# sender_einfach_12v.net
KiCad netlist of a schematic drawn in EAGLE
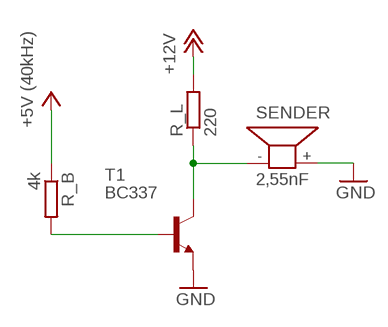
[diagram p0: schematic, sheet 1]

(export (version "E")
  (design (tool "Eeschema 10.0.6"))
  (components
    (comp (ref "R_B")
      (value "4k")
      (footprint "eagle-import:0309_12")
      (libsource (lib "eagle-import") (part "R-EU_0309/12"))
    )
    (comp (ref "R_L")
      (value "220")
      (footprint "eagle-import:0309_12")
      (libsource (lib "eagle-import") (part "R-EU_0309/12"))
    )
    (comp (ref "SENDER")
      (value "2,55nF")
      (footprint "eagle-import:AL11P")
      (libsource (lib "eagle-import") (part "AL11P"))
    )
    (comp (ref "T1")
      (value "BC337")
      (footprint "eagle-import:TO92")
      (libsource (lib "eagle-import") (part "BC337"))
    )
  )
  (nets
    (net (code "1") (name "+5V (40kHz)") (class "Default")
      (node (ref "R_B") (pin "1") (pinfunction "1_1") (pintype "passive"))
    )
    (net (code "2") (name "+12V") (class "Default")
      (node (ref "R_L") (pin "2") (pinfunction "2_2") (pintype "passive"))
    )
    (net (code "3") (name "GND") (class "Default")
      (node (ref "SENDER") (pin "+") (pinfunction "2_+") (pintype "passive"))
      (node (ref "T1") (pin "1") (pinfunction "E_1") (pintype "passive"))
    )
    (net (code "4") (name "Net-(SENDER-1)") (class "Default")
      (node (ref "R_L") (pin "1") (pinfunction "1_1") (pintype "passive"))
      (node (ref "SENDER") (pin "-") (pinfunction "1_-") (pintype "passive"))
      (node (ref "T1") (pin "3") (pinfunction "C_3") (pintype "passive"))
    )
    (net (code "5") (name "Net-(T1-B)") (class "Default")
      (node (ref "R_B") (pin "2") (pinfunction "2_2") (pintype "passive"))
      (node (ref "T1") (pin "2") (pinfunction "B_2") (pintype "passive"))
    )
  )
)
